# schemetic.net
KiCad netlist of a schematic drawn in Altium Designer
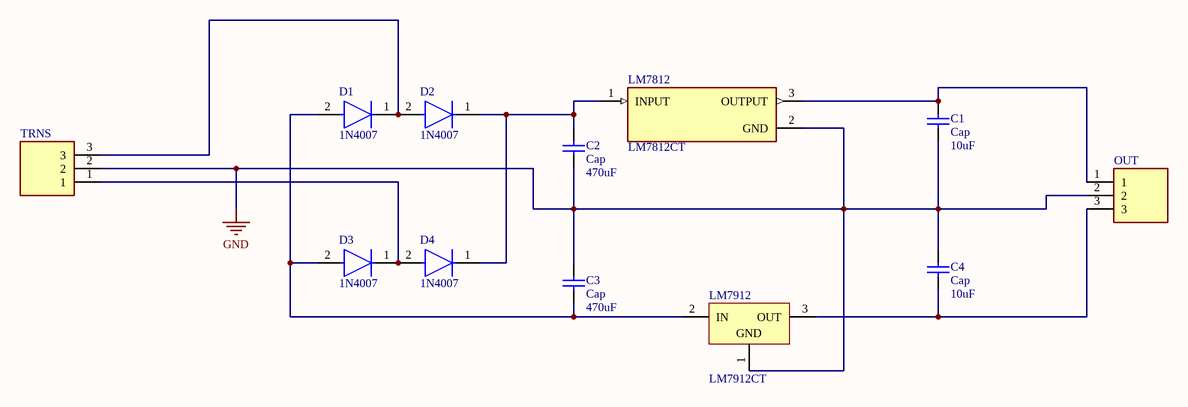
[diagram p0: schemetic.SchDoc]

(export (version "E")
  (design (tool "Eeschema 10.0.6"))
  (components
    (comp (ref "C1")
      (value "Cap")
      (footprint "RAD-0.3")
      (description "Capacitor")
      (fields (field (name "ALTIUM_VALUE") "10uF") (field (name "PUBLISHER") "Altium Limited"))
      (libsource (lib "Miscellaneous Devices") (part "Cap"))
    )
    (comp (ref "C2")
      (value "Cap")
      (footprint "RAD-0.3")
      (description "Capacitor")
      (fields (field (name "ALTIUM_VALUE") "470uF") (field (name "PUBLISHER") "Altium Limited"))
      (libsource (lib "Miscellaneous Devices") (part "Cap"))
    )
    (comp (ref "C3")
      (value "Cap")
      (footprint "RAD-0.3")
      (description "Capacitor")
      (fields (field (name "ALTIUM_VALUE") "470uF") (field (name "PUBLISHER") "Altium Limited"))
      (libsource (lib "Miscellaneous Devices") (part "Cap"))
    )
    (comp (ref "C4")
      (value "Cap")
      (footprint "RAD-0.3")
      (description "Capacitor")
      (fields (field (name "ALTIUM_VALUE") "10uF") (field (name "PUBLISHER") "Altium Limited"))
      (libsource (lib "Miscellaneous Devices") (part "Cap"))
    )
    (comp (ref "D1")
      (value "1N4007")
      (footprint "FP-017AG-MFG")
      (description "DIODE GEN PURP 100V 200MA DO35")
      (fields (field (name "VOLTAGE") "100V"))
      (libsource (lib "Altium Content Vault") (part "d7152d700b627762746794eb795d46e"))
    )
    (comp (ref "D2")
      (value "1N4007")
      (footprint "FP-017AG-MFG")
      (description "DIODE GEN PURP 100V 200MA DO35")
      (fields (field (name "VOLTAGE") "100V"))
      (libsource (lib "Altium Content Vault") (part "d7152d700b627762746794eb795d46e"))
    )
    (comp (ref "D3")
      (value "1N4007")
      (footprint "FP-017AG-MFG")
      (description "DIODE GEN PURP 100V 200MA DO35")
      (fields (field (name "VOLTAGE") "100V"))
      (libsource (lib "Altium Content Vault") (part "d7152d700b627762746794eb795d46e"))
    )
    (comp (ref "D4")
      (value "1N4007")
      (footprint "FP-017AG-MFG")
      (description "DIODE GEN PURP 100V 200MA DO35")
      (fields (field (name "VOLTAGE") "100V"))
      (libsource (lib "Altium Content Vault") (part "d7152d700b627762746794eb795d46e"))
    )
    (comp (ref "LM7812")
      (value "LM7812CT")
      (footprint "FP-TO220B03-MFG")
      (description "IC REG LINEAR 12V 1A TO220-3")
      (fields
        (field (name "OCTOPART") "https://octopart.com/lm7812ct-on+semiconductor-14383031")
        (field (name "OBSOLETE PART") "true")
      )
      (libsource (lib "Altium Content Vault") (part "6207a8f1a6b4db326a9e0a8a99b4969"))
    )
    (comp (ref "LM7912")
      (value "LM7912CT")
      (footprint "NDE0003A")
      (description "3-Terminal Negative Regulator, 3-pin TO-220")
      (fields (field (name "MANUFACTURER") "Texas Instruments"))
      (libsource (lib "Altium Content Vault") (part "PM-REG-LM7905-SIL3"))
    )
    (comp (ref "OUT")
      (value "~")
      (footprint "CUI_TBP01R2-508-03BE")
      (fields (field (name "MP") "TBP01R2-508-03BE") (field (name "MF") "{'manufacturer': u'CUI'}"))
      (libsource (lib "") (part "TBP01R2-508-03BE_1"))
    )
    (comp (ref "TRNS")
      (value "~")
      (footprint "CUI_TBP01R2-508-03BE")
      (fields (field (name "MP") "TBP01R2-508-03BE") (field (name "MF") "{'manufacturer': u'CUI'}"))
      (libsource (lib "TBP01R2-508-03BE") (part "TBP01R2-508-03BE"))
    )
  )
  (nets
    (net (code "1") (name "GND") (class "Default")
      (node (ref "C1") (pin "1") (pinfunction "1_1") (pintype "passive"))
      (node (ref "C2") (pin "1") (pinfunction "1_1") (pintype "passive"))
      (node (ref "C3") (pin "2") (pinfunction "2_2") (pintype "passive"))
      (node (ref "C4") (pin "2") (pinfunction "2_2") (pintype "passive"))
      (node (ref "LM7812") (pin "2") (pinfunction "GND_2") (pintype "power_in"))
      (node (ref "LM7912") (pin "1") (pinfunction "GND_1") (pintype "power_in"))
      (node (ref "OUT") (pin "2") (pinfunction "2_2") (pintype "passive"))
      (node (ref "TRNS") (pin "2") (pinfunction "2_2") (pintype "passive"))
    )
    (net (code "2") (name "Net-(D1-A)") (class "Default")
      (node (ref "C3") (pin "1") (pinfunction "1_1") (pintype "passive"))
      (node (ref "D1") (pin "2") (pinfunction "A_2") (pintype "passive"))
      (node (ref "D3") (pin "2") (pinfunction "A_2") (pintype "passive"))
      (node (ref "LM7912") (pin "2") (pinfunction "IN_2") (pintype "power_in"))
    )
    (net (code "3") (name "Net-(D1-C)") (class "Default")
      (node (ref "D1") (pin "1") (pinfunction "C_1") (pintype "passive"))
      (node (ref "D2") (pin "2") (pinfunction "A_2") (pintype "passive"))
      (node (ref "TRNS") (pin "3") (pinfunction "3_3") (pintype "passive"))
    )
    (net (code "4") (name "Net-(D2-C)") (class "Default")
      (node (ref "C2") (pin "2") (pinfunction "2_2") (pintype "passive"))
      (node (ref "D2") (pin "1") (pinfunction "C_1") (pintype "passive"))
      (node (ref "D4") (pin "1") (pinfunction "C_1") (pintype "passive"))
      (node (ref "LM7812") (pin "1") (pinfunction "INPUT_1") (pintype "input"))
    )
    (net (code "5") (name "Net-(D3-C)") (class "Default")
      (node (ref "D3") (pin "1") (pinfunction "C_1") (pintype "passive"))
      (node (ref "D4") (pin "2") (pinfunction "A_2") (pintype "passive"))
      (node (ref "TRNS") (pin "1") (pinfunction "1_1") (pintype "passive"))
    )
    (net (code "6") (name "Net-(LM7812-OUTPUT)") (class "Default")
      (node (ref "C1") (pin "2") (pinfunction "2_2") (pintype "passive"))
      (node (ref "LM7812") (pin "3") (pinfunction "OUTPUT_3") (pintype "output"))
      (node (ref "OUT") (pin "1") (pinfunction "1_1") (pintype "passive"))
    )
    (net (code "7") (name "Net-(LM7912-OUT)") (class "Default")
      (node (ref "C4") (pin "1") (pinfunction "1_1") (pintype "passive"))
      (node (ref "LM7912") (pin "3") (pinfunction "OUT_3") (pintype "power_in"))
      (node (ref "OUT") (pin "3") (pinfunction "3_3") (pintype "passive"))
    )
  )
)
